# PowerStage.net
KiCad netlist of a schematic drawn in Altium Designer
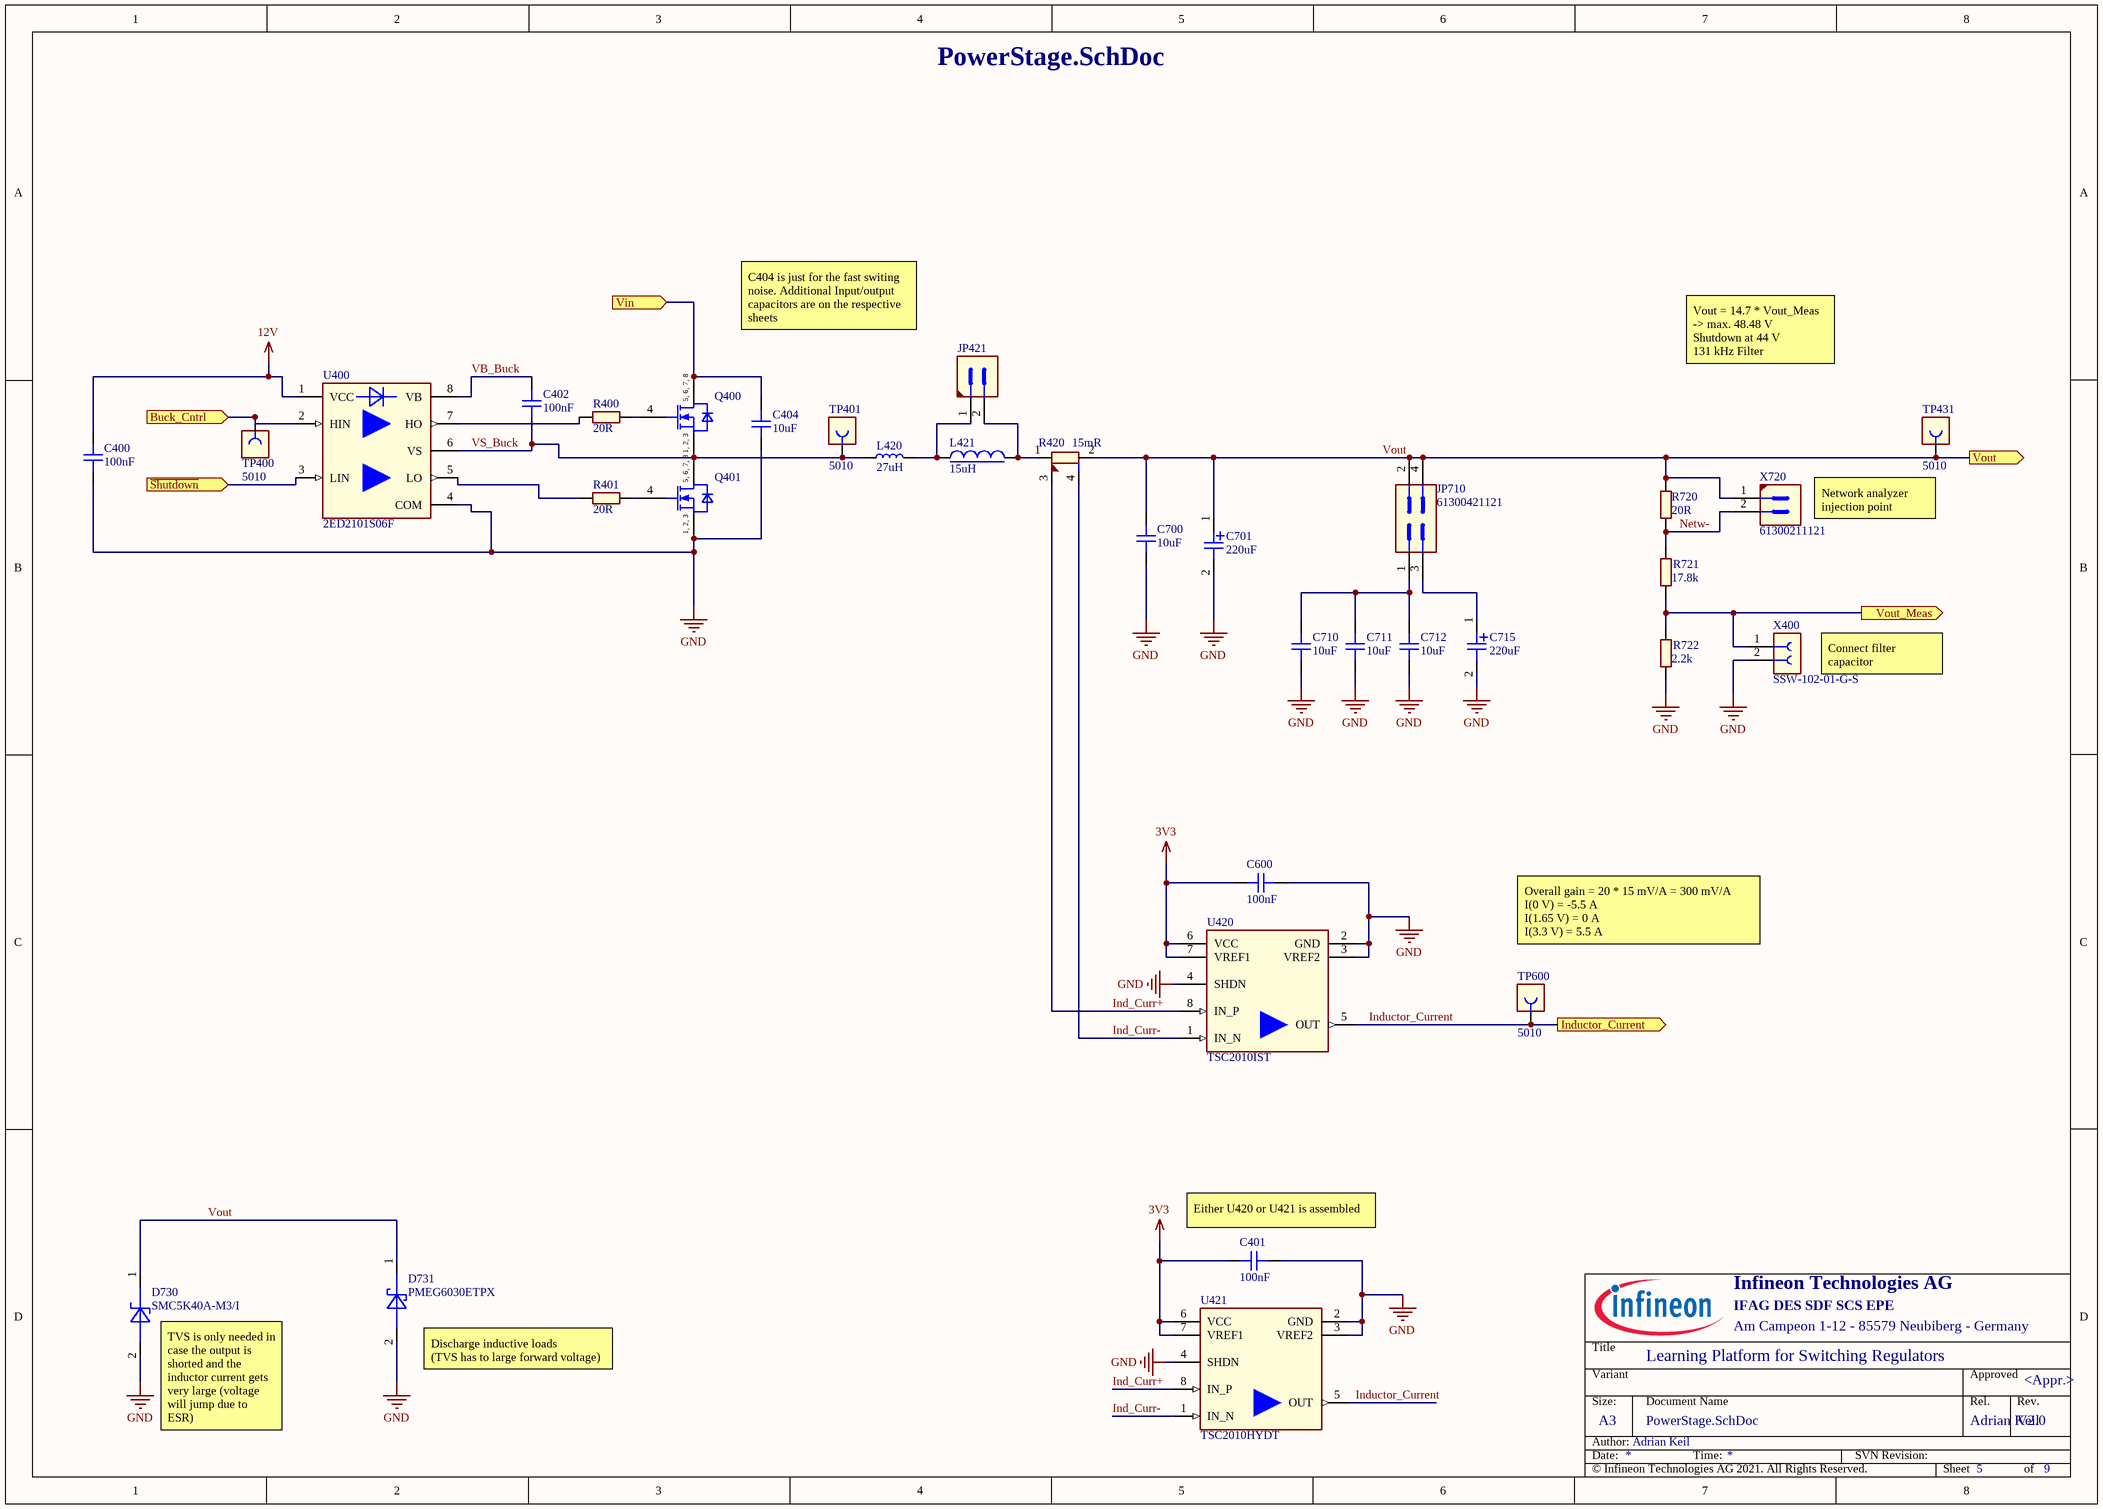
[diagram p0: PowerStage.SchDoc]

(export (version "E")
  (design (tool "Eeschema 10.0.6"))
  (components
    (comp (ref "C400")
      (value "100nF")
      (footprint "CAPC1608X90N-2")
      (description "CAP / CERA / 100nF / 50V / 10% / X7R (EIA) / -55°C to 125°C / 0603 / SMD / -")
      (fields (field (name "MANUFACTURER") "AVX"))
      (libsource (lib "PCBLibraryData") (part "CAP-SGL-STD-02P_00000001"))
    )
    (comp (ref "C401")
      (value "100nF")
      (footprint "CAPC1608X90N-2")
      (description "CAP / CERA / 100nF / 50V / 10% / X7R (EIA) / -55°C to 125°C / 0603 / SMD / -")
      (fields (field (name "MANUFACTURER") "AVX"))
      (libsource (lib "PCBLibraryData") (part "CAP-SGL-STD-02P_00000001"))
    )
    (comp (ref "C402")
      (value "100nF")
      (footprint "CAPC1608X90N-2")
      (description "CAP / CERA / 100nF / 50V / 10% / X7R (EIA) / -55°C to 125°C / 0603 / SMD / -")
      (fields (field (name "MANUFACTURER") "AVX"))
      (libsource (lib "PCBLibraryData") (part "CAP-SGL-STD-02P_00000001"))
    )
    (comp (ref "C404")
      (value "10uF")
      (footprint "CAPC3216X190N-1")
      (description "CAP / CERA / 10uF / 50V / 20% / X5R (EIA) / -55°C to 85°C / 1206 (3216) / SMD / -")
      (fields (field (name "MANUFACTURER") "Taiyo Yuden"))
      (libsource (lib "PCBLibraryData") (part "CAP-SGL-STD-02P_00000001"))
    )
    (comp (ref "C600")
      (value "100nF")
      (footprint "CAPC1608X90N-2")
      (description "CAP / CERA / 100nF / 50V / 10% / X7R (EIA) / -55°C to 125°C / 0603 / SMD / -")
      (fields (field (name "MANUFACTURER") "AVX"))
      (libsource (lib "PCBLibraryData") (part "CAP-SGL-STD-02P_00000001"))
    )
    (comp (ref "C700")
      (value "10uF")
      (footprint "CAPC3216X190N-1")
      (description "CAP / CERA / 10uF / 50V / 20% / X5R (EIA) / -55°C to 85°C / 1206 (3216) / SMD / -")
      (fields (field (name "MANUFACTURER") "Taiyo Yuden"))
      (libsource (lib "PCBLibraryData") (part "CAP-SGL-STD-02P_00000001"))
    )
    (comp (ref "C701")
      (value "220uF")
      (footprint "CAPAE1030X1050N-3")
      (fields (field (name "MANUFACTURER") "Nippon Chemi-Con"))
      (libsource (lib "PCBLibraryData") (part "CAP-SGL-POL-02P_00000002"))
    )
    (comp (ref "C710")
      (value "10uF")
      (footprint "CAPC3216X190N-1")
      (description "CAP / CERA / 10uF / 50V / 20% / X5R (EIA) / -55°C to 85°C / 1206 (3216) / SMD / -")
      (fields (field (name "MANUFACTURER") "Taiyo Yuden"))
      (libsource (lib "PCBLibraryData") (part "CAP-SGL-STD-02P_00000001"))
    )
    (comp (ref "C711")
      (value "10uF")
      (footprint "CAPC3216X190N-1")
      (description "CAP / CERA / 10uF / 50V / 20% / X5R (EIA) / -55°C to 85°C / 1206 (3216) / SMD / -")
      (fields (field (name "MANUFACTURER") "Taiyo Yuden"))
      (libsource (lib "PCBLibraryData") (part "CAP-SGL-STD-02P_00000001"))
    )
    (comp (ref "C712")
      (value "10uF")
      (footprint "CAPC3216X190N-1")
      (description "CAP / CERA / 10uF / 50V / 20% / X5R (EIA) / -55°C to 85°C / 1206 (3216) / SMD / -")
      (fields (field (name "MANUFACTURER") "Taiyo Yuden"))
      (libsource (lib "PCBLibraryData") (part "CAP-SGL-STD-02P_00000001"))
    )
    (comp (ref "C715")
      (value "220uF")
      (footprint "CAPAE1030X1050N-3")
      (fields (field (name "MANUFACTURER") "Nippon Chemi-Con"))
      (libsource (lib "PCBLibraryData") (part "CAP-SGL-POL-02P_00000002"))
    )
    (comp (ref "D730")
      (value "SMC5K40A-M3/I")
      (footprint "DIOM7959X262N")
      (description "Surface Mount Transient Voltage Suppressors, Unidirectional, Very Fast Response Time")
      (fields (field (name "MANUFACTURER") "Vishay"))
      (libsource (lib "PCBLibraryData") (part "d_tvs_a"))
    )
    (comp (ref "D731")
      (value "PMEG6030ETPX")
      (footprint "SODFL4725X110N")
      (description "DIODE SCHOTTKY 60V 3A SOD128")
      (fields (field (name "MANUFACTURER") "Nexperia"))
      (libsource (lib "PCBLibraryData") (part "d_schottky_a"))
    )
    (comp (ref "JP421")
      (value "61300211121")
      (footprint "CON-M-THT-61300211121")
      (description "Header, 2.54mm Pitch, 2 pin, Vertical, Single Row")
      (fields
        (field (name "LEGACY PARTNUMBER") "CON01500943")
        (field (name "MANUFACTURER") "Wurth Elektronik")
      )
      (libsource (lib "") (part "Header 2_1"))
    )
    (comp (ref "JP710")
      (value "61300421121")
      (footprint "CON-M-THT-61300421121")
      (description "Header, 4pins, 2.54mm pitch, Board to Board")
      (fields (field (name "MANUFACTURER") "Wurth Elektronik"))
      (libsource (lib "PCBLibraryData") (part "Header 2X2"))
    )
    (comp (ref "L420")
      (value "27uH")
      (footprint "INDM120120X1000N")
      (fields (field (name "MANUFACTURER") "Wurth Elektronik"))
      (libsource (lib "PCBLibraryData") (part "IND-SGL-STD-02P_00000015"))
    )
    (comp (ref "L421")
      (value "15uH")
      (footprint "IND-SMD-SRP6060FA")
      (fields (field (name "MANUFACTURER") "Bourns"))
      (libsource (lib "PCBLibraryData") (part "IND-SGL-STD-COR-02P_00000016"))
    )
    (comp (ref "Q400")
      (value "igfet_n_ch_enh_dio_1s2s3s4g5d6d7d8d_8p")
      (footprint "INF-PG-PQFN-5X6BEG")
      (description "HEXFET Power MOSFET, VDS 60V, RDS(on) max 14.4 mO")
      (fields (field (name "MANUFACTURER") "Infineon Technologies"))
      (libsource (lib "PCBLibraryData") (part "igfet_n_ch_enh_dio_1s2s3s4g5d6d7d8d_8p"))
    )
    (comp (ref "Q401")
      (value "igfet_n_ch_enh_dio_1s2s3s4g5d6d7d8d_8p")
      (footprint "INF-PG-PQFN-5X6BEG")
      (description "HEXFET Power MOSFET, VDS 60V, RDS(on) max 14.4 mO")
      (fields (field (name "MANUFACTURER") "Infineon Technologies"))
      (libsource (lib "PCBLibraryData") (part "igfet_n_ch_enh_dio_1s2s3s4g5d6d7d8d_8p"))
    )
    (comp (ref "R400")
      (value "20R")
      (footprint "RESC1609X50N")
      (description "RES / STD / 20R / 100mW / 1% / 100ppm/K / -55°C to 155°C / 0603 / SMD / -")
      (fields (field (name "LEGACY PARTNUMBER") "RES01800947") (field (name "MANUFACTURER") "Vishay"))
      (libsource (lib "") (part "RES-SGL-STD-02P_00000006_1"))
    )
    (comp (ref "R401")
      (value "20R")
      (footprint "RESC1609X50N")
      (description "RES / STD / 20R / 100mW / 1% / 100ppm/K / -55°C to 155°C / 0603 / SMD / -")
      (fields (field (name "LEGACY PARTNUMBER") "RES01800947") (field (name "MANUFACTURER") "Vishay"))
      (libsource (lib "") (part "RES-SGL-STD-02P_00000006_1"))
    )
    (comp (ref "R420")
      (value "15mR")
      (footprint "RES-SMD-L4T12")
      (description "RES / STD / 15mR / 500mW / 1% / 75ppm/K / -55°C to 155°C / 1206 (3216) / SMD / -")
      (fields (field (name "MANUFACTURER") "Ohmite"))
      (libsource (lib "PCBLibraryData") (part "RES-SHT-STD-04P_00097BE5"))
    )
    (comp (ref "R720")
      (value "20R")
      (footprint "RESC1609X50N")
      (description "RES / STD / 20R / 100mW / 1% / 100ppm/K / -55°C to 155°C / 0603 / SMD / -")
      (fields (field (name "LEGACY PARTNUMBER") "RES01800947") (field (name "MANUFACTURER") "Vishay"))
      (libsource (lib "") (part "RES-SGL-STD-02P_00000006_2"))
    )
    (comp (ref "R721")
      (value "17.8k")
      (footprint "RESC1608X60N")
      (fields (field (name "MANUFACTURER") "Multicomp"))
      (libsource (lib "") (part "RES-SGL-STD-02P_00000006_2"))
    )
    (comp (ref "R722")
      (value "2.2k")
      (footprint "RESC1609X50N")
      (description "RES / STD / 2.2k / 100mW / 1% / 100ppm/K / -55°C to 155°C / 0603 / SMD / -")
      (fields (field (name "LEGACY PARTNUMBER") "RES01801179") (field (name "MANUFACTURER") "Vishay"))
      (libsource (lib "PCBLibraryData") (part "RES-SGL-STD-02P_00000006"))
    )
    (comp (ref "TP400")
      (value "5010")
      (footprint "CON-THT-TP-5010")
      (description "PC Test Point-Multipurpose THT, Red")
      (fields
        (field (name "LEGACY PARTNUMBER") "CON01500529")
        (field (name "MANUFACTURER") "Keystone Electronics Corp.")
      )
      (libsource (lib "PCBLibraryData") (part "connector_1_f"))
    )
    (comp (ref "TP401")
      (value "5010")
      (footprint "CON-THT-TP-5010")
      (description "PC Test Point-Multipurpose THT, Red")
      (fields
        (field (name "LEGACY PARTNUMBER") "CON01500529")
        (field (name "MANUFACTURER") "Keystone Electronics Corp.")
      )
      (libsource (lib "") (part "connector_1_f_1"))
    )
    (comp (ref "TP431")
      (value "5010")
      (footprint "CON-THT-TP-5010")
      (description "PC Test Point-Multipurpose THT, Red")
      (fields
        (field (name "LEGACY PARTNUMBER") "CON01500529")
        (field (name "MANUFACTURER") "Keystone Electronics Corp.")
      )
      (libsource (lib "") (part "connector_1_f_1"))
    )
    (comp (ref "TP600")
      (value "5010")
      (footprint "CON-THT-TP-5010")
      (description "PC Test Point-Multipurpose THT, Red")
      (fields
        (field (name "LEGACY PARTNUMBER") "CON01500529")
        (field (name "MANUFACTURER") "Keystone Electronics Corp.")
      )
      (libsource (lib "") (part "connector_1_f_1"))
    )
    (comp (ref "U400")
      (value "2ED2101S06F")
      (footprint "SOIC127P600X172-8N-1")
      (fields (field (name "MANUFACTURER") "Infineon Technologies"))
      (libsource (lib "PCBLibraryData") (part "2ED2106S06F"))
    )
    (comp (ref "U420")
      (value "TSC2010IST")
      (footprint "SOIC127P600X175-8N-16")
      (description "Precision bidirectional current sense amplifier")
      (fields (field (name "MANUFACTURER") "STMicroelectronics"))
      (libsource (lib "PCBLibraryData") (part "TSC201XHYDT"))
    )
    (comp (ref "U421")
      (value "TSC2010HYDT")
      (footprint "SOIC127P600X175-8N-16")
      (description "Precision bidirectional current sense amplifier")
      (fields (field (name "MANUFACTURER") "STMicroelectronics"))
      (libsource (lib "PCBLibraryData") (part "TSC201XHYDT"))
    )
    (comp (ref "X400")
      (value "SSW-102-01-G-S")
      (footprint "CON-F-THT-SSW-102-01-G-S")
      (description "Through Hole .025'' SQ Post Socket, 2.54mm pitch, 2 Pins")
      (fields (field (name "MANUFACTURER") "Samtec"))
      (libsource (lib "PCBLibraryData") (part "Socket 2"))
    )
    (comp (ref "X720")
      (value "61300211121")
      (footprint "CON-M-THT-61300211121")
      (description "Header, 2.54mm Pitch, 2 pin, Vertical, Single Row")
      (fields
        (field (name "LEGACY PARTNUMBER") "CON01500943")
        (field (name "MANUFACTURER") "Wurth Elektronik")
      )
      (libsource (lib "PCBLibraryData") (part "Header 2"))
    )
  )
  (nets
    (net (code "1") (name "/Buck_Cntrl") (class "Default")
      (node (ref "TP400") (pin "1") (pinfunction "1_1") (pintype "passive"))
      (node (ref "U400") (pin "2") (pinfunction "HIN_2") (pintype "input"))
    )
    (net (code "2") (name "/Ind_Curr+") (class "Default")
      (node (ref "R420") (pin "3") (pinfunction "I1_3") (pintype "passive"))
      (node (ref "U420") (pin "8") (pinfunction "IN_P_8") (pintype "input"))
      (node (ref "U421") (pin "8") (pinfunction "IN_P_8") (pintype "input"))
    )
    (net (code "3") (name "/Ind_Curr-") (class "Default")
      (node (ref "R420") (pin "4") (pinfunction "I2_4") (pintype "passive"))
      (node (ref "U420") (pin "1") (pinfunction "IN_N_1") (pintype "input"))
      (node (ref "U421") (pin "1") (pinfunction "IN_N_1") (pintype "input"))
    )
    (net (code "4") (name "/Inductor_Current") (class "Default")
      (node (ref "TP600") (pin "1") (pinfunction "1_1") (pintype "passive"))
      (node (ref "U420") (pin "5") (pinfunction "OUT_5") (pintype "output"))
      (node (ref "U421") (pin "5") (pinfunction "OUT_5") (pintype "output"))
    )
    (net (code "5") (name "/Netw-") (class "Default")
      (node (ref "R720") (pin "1") (pinfunction "1_1") (pintype "passive"))
      (node (ref "R721") (pin "2") (pinfunction "2_2") (pintype "passive"))
      (node (ref "X720") (pin "2") (pinfunction "2_2") (pintype "passive"))
    )
    (net (code "6") (name "/Shutdown") (class "Default")
      (node (ref "U400") (pin "3") (pinfunction "LIN_3") (pintype "input"))
    )
    (net (code "7") (name "/VB_Buck") (class "Default")
      (node (ref "C402") (pin "2") (pinfunction "2_2") (pintype "passive"))
      (node (ref "U400") (pin "8") (pinfunction "VB_8") (pintype "power_in"))
    )
    (net (code "8") (name "/VS_Buck") (class "Default")
      (node (ref "C402") (pin "1") (pinfunction "1_1") (pintype "passive"))
      (node (ref "L420") (pin "1") (pinfunction "1_1") (pintype "passive"))
      (node (ref "Q400") (pin "1") (pinfunction "SOURCE_1") (pintype "passive"))
      (node (ref "Q400") (pin "2") (pinfunction "SOURCE_2") (pintype "passive"))
      (node (ref "Q400") (pin "3") (pinfunction "SOURCE_3") (pintype "passive"))
      (node (ref "Q401") (pin "5") (pinfunction "DRAIN_5") (pintype "passive"))
      (node (ref "Q401") (pin "6") (pinfunction "DRAIN_6") (pintype "passive"))
      (node (ref "Q401") (pin "7") (pinfunction "DRAIN_7") (pintype "passive"))
      (node (ref "Q401") (pin "8") (pinfunction "DRAIN_8") (pintype "passive"))
      (node (ref "TP401") (pin "1") (pinfunction "1_1") (pintype "passive"))
      (node (ref "U400") (pin "6") (pinfunction "VS_6") (pintype "power_in"))
    )
    (net (code "9") (name "/Vin") (class "Default")
      (node (ref "C404") (pin "2") (pinfunction "2_2") (pintype "passive"))
      (node (ref "Q400") (pin "5") (pinfunction "DRAIN_5") (pintype "passive"))
      (node (ref "Q400") (pin "6") (pinfunction "DRAIN_6") (pintype "passive"))
      (node (ref "Q400") (pin "7") (pinfunction "DRAIN_7") (pintype "passive"))
      (node (ref "Q400") (pin "8") (pinfunction "DRAIN_8") (pintype "passive"))
    )
    (net (code "10") (name "/Vout") (class "Default")
      (node (ref "C700") (pin "2") (pinfunction "2_2") (pintype "passive"))
      (node (ref "C701") (pin "1") (pinfunction "1_1") (pintype "passive"))
      (node (ref "D730") (pin "1") (pinfunction "CATHODE_1") (pintype "passive"))
      (node (ref "D731") (pin "1") (pinfunction "Cathode_1") (pintype "passive"))
      (node (ref "JP710") (pin "2") (pinfunction "2_2") (pintype "passive"))
      (node (ref "JP710") (pin "4") (pinfunction "4_4") (pintype "passive"))
      (node (ref "R420") (pin "2") (pinfunction "V2_2") (pintype "passive"))
      (node (ref "R720") (pin "2") (pinfunction "2_2") (pintype "passive"))
      (node (ref "TP431") (pin "1") (pinfunction "1_1") (pintype "passive"))
      (node (ref "X720") (pin "1") (pinfunction "1_1") (pintype "passive"))
    )
    (net (code "11") (name "/Vout_Meas") (class "Default")
      (node (ref "R721") (pin "1") (pinfunction "1_1") (pintype "passive"))
      (node (ref "R722") (pin "1") (pinfunction "1_1") (pintype "passive"))
      (node (ref "X400") (pin "1") (pinfunction "1_1") (pintype "passive"))
    )
    (net (code "12") (name "3V3") (class "Default")
      (node (ref "C401") (pin "2") (pinfunction "2_2") (pintype "passive"))
      (node (ref "C600") (pin "2") (pinfunction "2_2") (pintype "passive"))
      (node (ref "U420") (pin "6") (pinfunction "VCC_6") (pintype "power_in"))
      (node (ref "U420") (pin "7") (pinfunction "VREF1_7") (pintype "power_in"))
      (node (ref "U421") (pin "6") (pinfunction "VCC_6") (pintype "power_in"))
      (node (ref "U421") (pin "7") (pinfunction "VREF1_7") (pintype "power_in"))
    )
    (net (code "13") (name "12V") (class "Default")
      (node (ref "C400") (pin "2") (pinfunction "2_2") (pintype "passive"))
      (node (ref "U400") (pin "1") (pinfunction "VCC_1") (pintype "power_in"))
    )
    (net (code "14") (name "GND") (class "Default")
      (node (ref "C400") (pin "1") (pinfunction "1_1") (pintype "passive"))
      (node (ref "C401") (pin "1") (pinfunction "1_1") (pintype "passive"))
      (node (ref "C404") (pin "1") (pinfunction "1_1") (pintype "passive"))
      (node (ref "C600") (pin "1") (pinfunction "1_1") (pintype "passive"))
      (node (ref "C700") (pin "1") (pinfunction "1_1") (pintype "passive"))
      (node (ref "C701") (pin "2") (pinfunction "2_2") (pintype "passive"))
      (node (ref "C710") (pin "1") (pinfunction "1_1") (pintype "passive"))
      (node (ref "C711") (pin "1") (pinfunction "1_1") (pintype "passive"))
      (node (ref "C712") (pin "1") (pinfunction "1_1") (pintype "passive"))
      (node (ref "C715") (pin "2") (pinfunction "2_2") (pintype "passive"))
      (node (ref "D730") (pin "2") (pinfunction "ANODE_2") (pintype "passive"))
      (node (ref "D731") (pin "2") (pinfunction "Anode_2") (pintype "passive"))
      (node (ref "Q401") (pin "1") (pinfunction "SOURCE_1") (pintype "passive"))
      (node (ref "Q401") (pin "2") (pinfunction "SOURCE_2") (pintype "passive"))
      (node (ref "Q401") (pin "3") (pinfunction "SOURCE_3") (pintype "passive"))
      (node (ref "R722") (pin "2") (pinfunction "2_2") (pintype "passive"))
      (node (ref "U400") (pin "4") (pinfunction "COM_4") (pintype "power_in"))
      (node (ref "U420") (pin "2") (pinfunction "GND_2") (pintype "power_in"))
      (node (ref "U420") (pin "3") (pinfunction "VREF2_3") (pintype "power_in"))
      (node (ref "U420") (pin "4") (pinfunction "SHDN_4") (pintype "passive"))
      (node (ref "U421") (pin "2") (pinfunction "GND_2") (pintype "power_in"))
      (node (ref "U421") (pin "3") (pinfunction "VREF2_3") (pintype "power_in"))
      (node (ref "U421") (pin "4") (pinfunction "SHDN_4") (pintype "passive"))
      (node (ref "X400") (pin "2") (pinfunction "2_2") (pintype "passive"))
    )
    (net (code "15") (name "Net-(C710-Pad2)") (class "Default")
      (node (ref "C710") (pin "2") (pinfunction "2_2") (pintype "passive"))
      (node (ref "C711") (pin "2") (pinfunction "2_2") (pintype "passive"))
      (node (ref "C712") (pin "2") (pinfunction "2_2") (pintype "passive"))
      (node (ref "JP710") (pin "1") (pinfunction "1_1") (pintype "passive"))
    )
    (net (code "16") (name "Net-(C715-Pad1)") (class "Default")
      (node (ref "C715") (pin "1") (pinfunction "1_1") (pintype "passive"))
      (node (ref "JP710") (pin "3") (pinfunction "3_3") (pintype "passive"))
    )
    (net (code "17") (name "Net-(JP421-Pad1)") (class "Default")
      (node (ref "JP421") (pin "1") (pinfunction "1_1") (pintype "passive"))
      (node (ref "L420") (pin "2") (pinfunction "2_2") (pintype "passive"))
      (node (ref "L421") (pin "1") (pinfunction "1_1") (pintype "passive"))
    )
    (net (code "18") (name "Net-(Q400-GATE)") (class "Default")
      (node (ref "Q400") (pin "4") (pinfunction "GATE_4") (pintype "passive"))
      (node (ref "R400") (pin "1") (pinfunction "1_1") (pintype "passive"))
    )
    (net (code "19") (name "Net-(Q401-GATE)") (class "Default")
      (node (ref "Q401") (pin "4") (pinfunction "GATE_4") (pintype "passive"))
      (node (ref "R401") (pin "1") (pinfunction "1_1") (pintype "passive"))
    )
    (net (code "20") (name "Net-(R420-V1)") (class "Default")
      (node (ref "JP421") (pin "2") (pinfunction "2_2") (pintype "passive"))
      (node (ref "L421") (pin "2") (pinfunction "2_2") (pintype "passive"))
      (node (ref "R420") (pin "1") (pinfunction "V1_1") (pintype "passive"))
    )
    (net (code "21") (name "Net-(U400-HO)") (class "Default")
      (node (ref "R400") (pin "2") (pinfunction "2_2") (pintype "passive"))
      (node (ref "U400") (pin "7") (pinfunction "HO_7") (pintype "output"))
    )
    (net (code "22") (name "Net-(U400-LO)") (class "Default")
      (node (ref "R401") (pin "2") (pinfunction "2_2") (pintype "passive"))
      (node (ref "U400") (pin "5") (pinfunction "LO_5") (pintype "output"))
    )
  )
)
